# ADS1299_-_Breakout.net
KiCad netlist of a schematic drawn in EAGLE
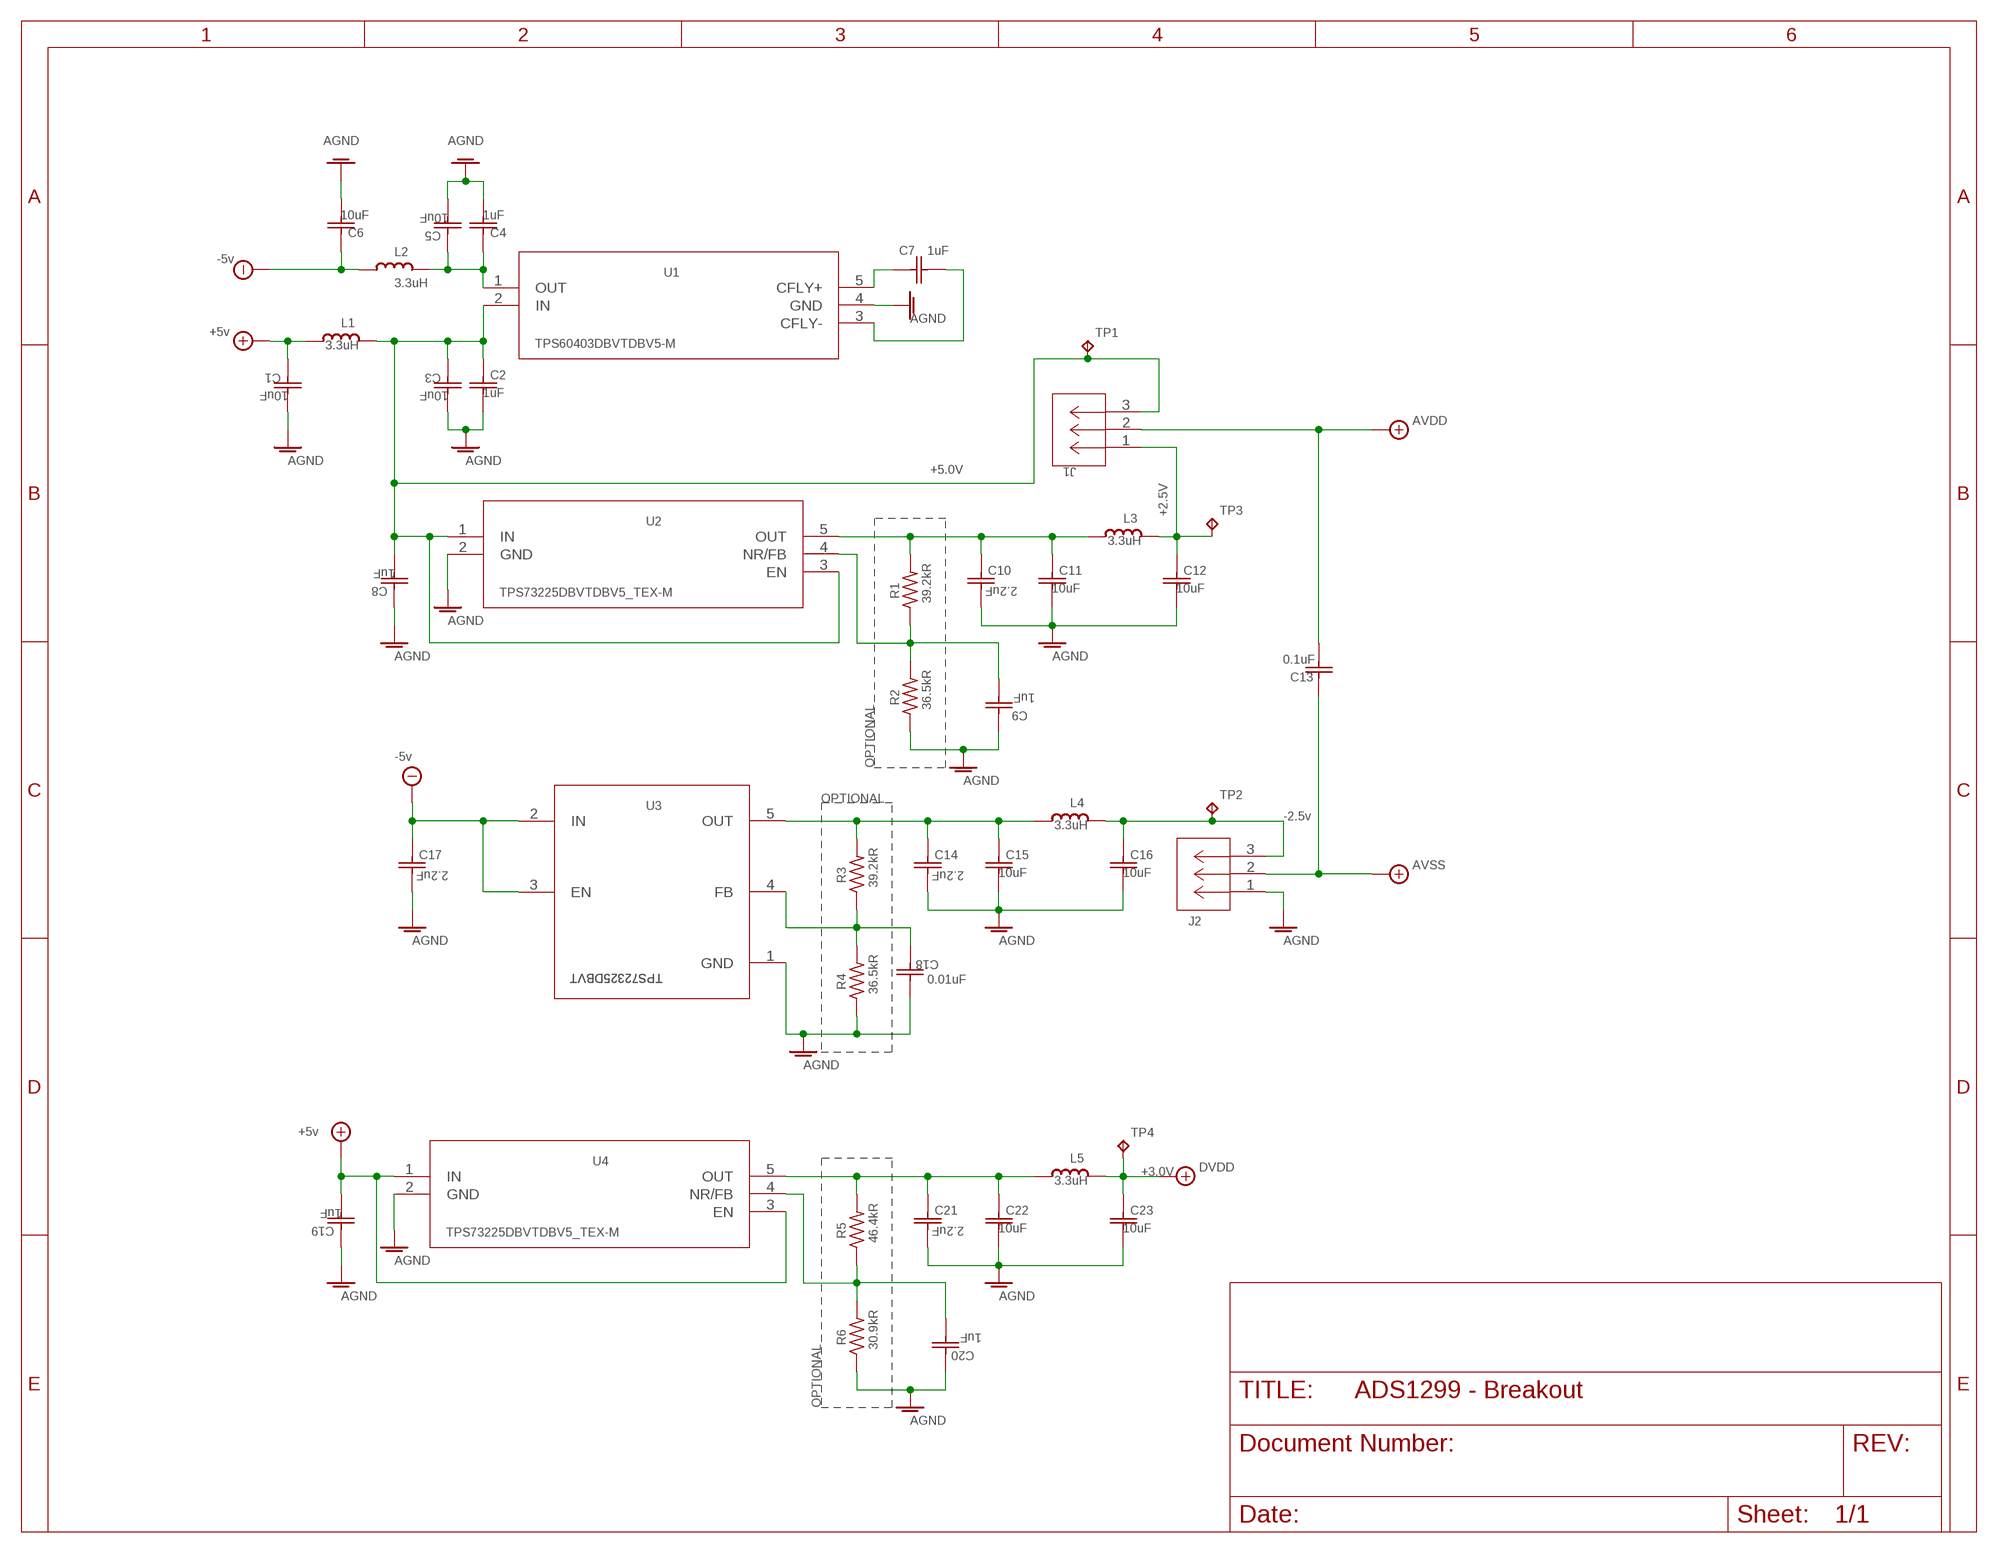
[diagram p0: schematic, sheet 1]

(export (version "E")
  (design (tool "Eeschema 10.0.6"))
  (components
    (comp (ref "C1")
      (value "10uF")
      (footprint "eagle-import:G-21_MUR-M")
      (fields
        (field (name "MANUFACTURER_PART_NUMBER") "GRM219R61A106KE44D")
        (field (name "COPYRIGHT") "Copyright (C) 2015 Accelerated Designs. All rights reserved")
      )
      (libsource (lib "eagle-import") (part "GRM219R61A106KE44DG-21_MUR-M"))
    )
    (comp (ref "C2")
      (value "1uF")
      (footprint "eagle-import:G-188_MUR-M")
      (fields
        (field (name "MANUFACTURER_PART_NUMBER") "GRM188R61E105KA12D")
        (field (name "COPYRIGHT") "Copyright (C) 2015 Accelerated Designs. All rights reserved")
      )
      (libsource (lib "eagle-import") (part "GRM188R61E105KA12DG-188_MUR-M"))
    )
    (comp (ref "C3")
      (value "10uF")
      (footprint "eagle-import:G-21_MUR-M")
      (fields
        (field (name "MANUFACTURER_PART_NUMBER") "GRM219R61A106KE44D")
        (field (name "COPYRIGHT") "Copyright (C) 2015 Accelerated Designs. All rights reserved")
      )
      (libsource (lib "eagle-import") (part "GRM219R61A106KE44DG-21_MUR-M"))
    )
    (comp (ref "C4")
      (value "1uF")
      (footprint "eagle-import:G-188_MUR-M")
      (fields
        (field (name "MANUFACTURER_PART_NUMBER") "GRM188R61E105KA12D")
        (field (name "COPYRIGHT") "Copyright (C) 2015 Accelerated Designs. All rights reserved")
      )
      (libsource (lib "eagle-import") (part "GRM188R61E105KA12DG-188_MUR-M"))
    )
    (comp (ref "C5")
      (value "10uF")
      (footprint "eagle-import:G-21_MUR-M")
      (fields
        (field (name "MANUFACTURER_PART_NUMBER") "GRM219R61A106KE44D")
        (field (name "COPYRIGHT") "Copyright (C) 2015 Accelerated Designs. All rights reserved")
      )
      (libsource (lib "eagle-import") (part "GRM219R61A106KE44DG-21_MUR-M"))
    )
    (comp (ref "C6")
      (value "10uF")
      (footprint "eagle-import:G-21_MUR-M")
      (fields
        (field (name "MANUFACTURER_PART_NUMBER") "GRM219R61A106KE44D")
        (field (name "COPYRIGHT") "Copyright (C) 2015 Accelerated Designs. All rights reserved")
      )
      (libsource (lib "eagle-import") (part "GRM219R61A106KE44DG-21_MUR-M"))
    )
    (comp (ref "C7")
      (value "1uF")
      (footprint "eagle-import:G-188_MUR-M")
      (fields
        (field (name "MANUFACTURER_PART_NUMBER") "GRM188R61E105KA12D")
        (field (name "COPYRIGHT") "Copyright (C) 2015 Accelerated Designs. All rights reserved")
      )
      (libsource (lib "eagle-import") (part "GRM188R61E105KA12DG-188_MUR-M"))
    )
    (comp (ref "C8")
      (value "1uF")
      (footprint "eagle-import:G-188_MUR-M")
      (fields
        (field (name "MANUFACTURER_PART_NUMBER") "GRM188R61E105KA12D")
        (field (name "COPYRIGHT") "Copyright (C) 2015 Accelerated Designs. All rights reserved")
      )
      (libsource (lib "eagle-import") (part "GRM188R61E105KA12DG-188_MUR-M"))
    )
    (comp (ref "C9")
      (value "1uF")
      (footprint "eagle-import:G-188_MUR-M")
      (fields
        (field (name "MANUFACTURER_PART_NUMBER") "GRM188R61E105KA12D")
        (field (name "COPYRIGHT") "Copyright (C) 2015 Accelerated Designs. All rights reserved")
      )
      (libsource (lib "eagle-import") (part "GRM188R61E105KA12DG-188_MUR-M"))
    )
    (comp (ref "C10")
      (value "2.2uF")
      (footprint "eagle-import:CAP_GCJ1888_MUR-M")
      (fields
        (field (name "MANUFACTURER_PART_NUMBER") "GRM185R60J225KE26D")
        (field (name "COPYRIGHT") "Copyright (C) 2015 Accelerated Designs. All rights reserved")
      )
      (libsource (lib "eagle-import") (part "GRM185R60J225KE26DCAP_GCJ1888_MUR-M"))
    )
    (comp (ref "C11")
      (value "10uF")
      (footprint "eagle-import:G-21_MUR-M")
      (fields
        (field (name "MANUFACTURER_PART_NUMBER") "GRM219R61A106KE44D")
        (field (name "COPYRIGHT") "Copyright (C) 2015 Accelerated Designs. All rights reserved")
      )
      (libsource (lib "eagle-import") (part "GRM219R61A106KE44DG-21_MUR-M"))
    )
    (comp (ref "C12")
      (value "10uF")
      (footprint "eagle-import:G-21_MUR-M")
      (fields
        (field (name "MANUFACTURER_PART_NUMBER") "GRM219R61A106KE44D")
        (field (name "COPYRIGHT") "Copyright (C) 2015 Accelerated Designs. All rights reserved")
      )
      (libsource (lib "eagle-import") (part "GRM219R61A106KE44DG-21_MUR-M"))
    )
    (comp (ref "C13")
      (value "0.1uF")
      (footprint "eagle-import:CAP_GRM_188_MUR-M")
      (fields
        (field (name "DIGIKEYPARTNUMBER") "490-1519-6-ND")
        (field (name "MANUFACTURER_PART_NUMBER") "GRM188R71H104KA93D")
        (field (name "TOLERANCE") "0.1")
        (field (name "COPYRIGHT") "Copyright (C) 2015 Accelerated Designs. All rights reserved")
      )
      (libsource (lib "eagle-import") (part "GRM188R71H104KA93DCAP_GRM_188_MUR-M"))
    )
    (comp (ref "C14")
      (value "2.2uF")
      (footprint "eagle-import:CAP_GCJ1888_MUR-M")
      (fields
        (field (name "MANUFACTURER_PART_NUMBER") "GRM185R60J225KE26D")
        (field (name "COPYRIGHT") "Copyright (C) 2015 Accelerated Designs. All rights reserved")
      )
      (libsource (lib "eagle-import") (part "GRM185R60J225KE26DCAP_GCJ1888_MUR-M"))
    )
    (comp (ref "C15")
      (value "10uF")
      (footprint "eagle-import:G-21_MUR-M")
      (fields
        (field (name "MANUFACTURER_PART_NUMBER") "GRM219R61A106KE44D")
        (field (name "COPYRIGHT") "Copyright (C) 2015 Accelerated Designs. All rights reserved")
      )
      (libsource (lib "eagle-import") (part "GRM219R61A106KE44DG-21_MUR-M"))
    )
    (comp (ref "C16")
      (value "10uF")
      (footprint "eagle-import:G-21_MUR-M")
      (fields
        (field (name "MANUFACTURER_PART_NUMBER") "GRM219R61A106KE44D")
        (field (name "COPYRIGHT") "Copyright (C) 2015 Accelerated Designs. All rights reserved")
      )
      (libsource (lib "eagle-import") (part "GRM219R61A106KE44DG-21_MUR-M"))
    )
    (comp (ref "C17")
      (value "2.2uF")
      (footprint "eagle-import:CAP_GCJ1888_MUR-M")
      (fields
        (field (name "MANUFACTURER_PART_NUMBER") "GRM185R60J225KE26D")
        (field (name "COPYRIGHT") "Copyright (C) 2015 Accelerated Designs. All rights reserved")
      )
      (libsource (lib "eagle-import") (part "GRM185R60J225KE26DCAP_GCJ1888_MUR-M"))
    )
    (comp (ref "C18")
      (value "0.01uF")
      (footprint "eagle-import:G-188_MUR-M")
      (fields
        (field (name "MANUFACTURER_PART_NUMBER") "GRM188R71H472KA01D")
        (field (name "COPYRIGHT") "Copyright (C) 2015 Accelerated Designs. All rights reserved")
      )
      (libsource (lib "eagle-import") (part "GRM188R71H472KA01DG-188_MUR-M"))
    )
    (comp (ref "C19")
      (value "1uF")
      (footprint "eagle-import:G-188_MUR-M")
      (fields
        (field (name "MANUFACTURER_PART_NUMBER") "GRM188R61E105KA12D")
        (field (name "COPYRIGHT") "Copyright (C) 2015 Accelerated Designs. All rights reserved")
      )
      (libsource (lib "eagle-import") (part "GRM188R61E105KA12DG-188_MUR-M"))
    )
    (comp (ref "C20")
      (value "1uF")
      (footprint "eagle-import:G-188_MUR-M")
      (fields
        (field (name "MANUFACTURER_PART_NUMBER") "GRM188R61E105KA12D")
        (field (name "COPYRIGHT") "Copyright (C) 2015 Accelerated Designs. All rights reserved")
      )
      (libsource (lib "eagle-import") (part "GRM188R61E105KA12DG-188_MUR-M"))
    )
    (comp (ref "C21")
      (value "2.2uF")
      (footprint "eagle-import:CAP_GCJ1888_MUR-M")
      (fields
        (field (name "MANUFACTURER_PART_NUMBER") "GRM185R60J225KE26D")
        (field (name "COPYRIGHT") "Copyright (C) 2015 Accelerated Designs. All rights reserved")
      )
      (libsource (lib "eagle-import") (part "GRM185R60J225KE26DCAP_GCJ1888_MUR-M"))
    )
    (comp (ref "C22")
      (value "10uF")
      (footprint "eagle-import:G-21_MUR-M")
      (fields
        (field (name "MANUFACTURER_PART_NUMBER") "GRM219R61A106KE44D")
        (field (name "COPYRIGHT") "Copyright (C) 2015 Accelerated Designs. All rights reserved")
      )
      (libsource (lib "eagle-import") (part "GRM219R61A106KE44DG-21_MUR-M"))
    )
    (comp (ref "C23")
      (value "10uF")
      (footprint "eagle-import:G-21_MUR-M")
      (fields
        (field (name "MANUFACTURER_PART_NUMBER") "GRM219R61A106KE44D")
        (field (name "COPYRIGHT") "Copyright (C) 2015 Accelerated Designs. All rights reserved")
      )
      (libsource (lib "eagle-import") (part "GRM219R61A106KE44DG-21_MUR-M"))
    )
    (comp (ref "J1")
      (value "TSW-103-07-T-S")
      (footprint "eagle-import:CON3_1X3_TU_TSW")
      (libsource (lib "eagle-import") (part "TSW-103-07-T-S"))
    )
    (comp (ref "J2")
      (value "TSW-103-07-T-S")
      (footprint "eagle-import:CON3_1X3_TU_TSW")
      (libsource (lib "eagle-import") (part "TSW-103-07-T-S"))
    )
    (comp (ref "L1")
      (value "3.3uH")
      (footprint "eagle-import:L0805")
      (libsource (lib "eagle-import") (part "L_0805"))
    )
    (comp (ref "L2")
      (value "3.3uH")
      (footprint "eagle-import:L0805")
      (libsource (lib "eagle-import") (part "L_0805"))
    )
    (comp (ref "L3")
      (value "3.3uH")
      (footprint "eagle-import:L0805")
      (libsource (lib "eagle-import") (part "L_0805"))
    )
    (comp (ref "L4")
      (value "3.3uH")
      (footprint "eagle-import:L0805")
      (libsource (lib "eagle-import") (part "L_0805"))
    )
    (comp (ref "L5")
      (value "3.3uH")
      (footprint "eagle-import:L0805")
      (libsource (lib "eagle-import") (part "L_0805"))
    )
    (comp (ref "R1")
      (value "39.2kR")
      (footprint "eagle-import:R0603")
      (libsource (lib "eagle-import") (part "R-US_R0603"))
    )
    (comp (ref "R2")
      (value "36.5kR")
      (footprint "eagle-import:R0603")
      (libsource (lib "eagle-import") (part "R-US_R0603"))
    )
    (comp (ref "R3")
      (value "39.2kR")
      (footprint "eagle-import:R0603")
      (libsource (lib "eagle-import") (part "R-US_R0603"))
    )
    (comp (ref "R4")
      (value "36.5kR")
      (footprint "eagle-import:R0603")
      (libsource (lib "eagle-import") (part "R-US_R0603"))
    )
    (comp (ref "R5")
      (value "46.4kR")
      (footprint "eagle-import:R0603")
      (libsource (lib "eagle-import") (part "R-US_R0603"))
    )
    (comp (ref "R6")
      (value "30.9kR")
      (footprint "eagle-import:R0603")
      (libsource (lib "eagle-import") (part "R-US_R0603"))
    )
    (comp (ref "TP1")
      (value "TP-040")
      (footprint "eagle-import:TP-040")
      (libsource (lib "eagle-import") (part "TP-040"))
    )
    (comp (ref "TP2")
      (value "TP-040")
      (footprint "eagle-import:TP-040")
      (libsource (lib "eagle-import") (part "TP-040"))
    )
    (comp (ref "TP3")
      (value "TP-040")
      (footprint "eagle-import:TP-040")
      (libsource (lib "eagle-import") (part "TP-040"))
    )
    (comp (ref "TP4")
      (value "TP-040")
      (footprint "eagle-import:TP-040")
      (libsource (lib "eagle-import") (part "TP-040"))
    )
    (comp (ref "U1")
      (value "TPS60403DBVTDBV5-M")
      (footprint "eagle-import:DBV5-M")
      (fields
        (field (name "GENERIC_PART_NUMBER") "TPS60403")
        (field (name "MANUFACTURER") "Texas Instruments")
        (field (name "MANUFACTURER_PART_NUMBER") "TPS60403DBVT")
      )
      (libsource (lib "eagle-import") (part "TPS60403DBVTDBV5-M"))
    )
    (comp (ref "U2")
      (value "TPS73225DBVTDBV5_TEX-M")
      (footprint "eagle-import:DBV5_TEX-M")
      (fields
        (field (name "MANUFACTURER") "Texas Instruments")
        (field (name "MANUFACTURER_PART_NUMBER") "TPS73225DBVT")
      )
      (libsource (lib "eagle-import") (part "TPS73225DBVTDBV5_TEX-M"))
    )
    (comp (ref "U3")
      (value "TPS72325DBVT")
      (footprint "eagle-import:DBV0005A")
      (fields (field (name "MANUFACTURER") "Texas Instruments") (field (name "PARTNUMBER") "TPS72301DBV"))
      (libsource (lib "eagle-import") (part "TPS72325DBVT"))
    )
    (comp (ref "U4")
      (value "TPS73225DBVTDBV5_TEX-M")
      (footprint "eagle-import:DBV5_TEX-M")
      (fields
        (field (name "MANUFACTURER") "Texas Instruments")
        (field (name "MANUFACTURER_PART_NUMBER") "TPS73225DBVT")
      )
      (libsource (lib "eagle-import") (part "TPS73225DBVTDBV5_TEX-M"))
    )
  )
  (nets
    (net (code "1") (name "+5v") (class "Default")
      (node (ref "C1") (pin "2") (pinfunction "2_2") (pintype "passive"))
      (node (ref "C13") (pin "1") (pinfunction "1_1") (pintype "passive"))
      (node (ref "C13") (pin "2") (pinfunction "2_2") (pintype "passive"))
      (node (ref "C19") (pin "1") (pinfunction "1_1") (pintype "passive"))
      (node (ref "J1") (pin "2") (pinfunction "2_2") (pintype "passive"))
      (node (ref "J2") (pin "2") (pinfunction "2_2") (pintype "passive"))
      (node (ref "L1") (pin "2") (pinfunction "2_2") (pintype "passive"))
      (node (ref "U4") (pin "1") (pinfunction "IN_1") (pintype "input"))
      (node (ref "U4") (pin "3") (pinfunction "EN_3") (pintype "passive"))
    )
    (net (code "2") (name "-5v") (class "Default")
      (node (ref "C17") (pin "2") (pinfunction "2_2") (pintype "passive"))
      (node (ref "C6") (pin "1") (pinfunction "1_1") (pintype "passive"))
      (node (ref "L2") (pin "2") (pinfunction "2_2") (pintype "passive"))
      (node (ref "U3") (pin "2") (pinfunction "IN_2") (pintype "power_in"))
      (node (ref "U3") (pin "3") (pinfunction "EN_3") (pintype "input"))
    )
    (net (code "3") (name "/+2.5V") (class "Default")
      (node (ref "C12") (pin "2") (pinfunction "2_2") (pintype "passive"))
      (node (ref "J1") (pin "1") (pinfunction "1_1") (pintype "passive"))
      (node (ref "L3") (pin "1") (pinfunction "1_1") (pintype "passive"))
      (node (ref "TP3") (pin "1") (pinfunction "1_1") (pintype "passive"))
    )
    (net (code "4") (name "AGND") (class "Default")
      (node (ref "C1") (pin "1") (pinfunction "1_1") (pintype "passive"))
      (node (ref "C10") (pin "1") (pinfunction "1_1") (pintype "passive"))
      (node (ref "C11") (pin "1") (pinfunction "1_1") (pintype "passive"))
      (node (ref "C12") (pin "1") (pinfunction "1_1") (pintype "passive"))
      (node (ref "C14") (pin "1") (pinfunction "1_1") (pintype "passive"))
      (node (ref "C15") (pin "1") (pinfunction "1_1") (pintype "passive"))
      (node (ref "C16") (pin "1") (pinfunction "1_1") (pintype "passive"))
      (node (ref "C17") (pin "1") (pinfunction "1_1") (pintype "passive"))
      (node (ref "C18") (pin "1") (pinfunction "1_1") (pintype "passive"))
      (node (ref "C19") (pin "2") (pinfunction "2_2") (pintype "passive"))
      (node (ref "C2") (pin "2") (pinfunction "2_2") (pintype "passive"))
      (node (ref "C20") (pin "2") (pinfunction "2_2") (pintype "passive"))
      (node (ref "C21") (pin "1") (pinfunction "1_1") (pintype "passive"))
      (node (ref "C22") (pin "1") (pinfunction "1_1") (pintype "passive"))
      (node (ref "C23") (pin "1") (pinfunction "1_1") (pintype "passive"))
      (node (ref "C3") (pin "2") (pinfunction "2_2") (pintype "passive"))
      (node (ref "C4") (pin "2") (pinfunction "2_2") (pintype "passive"))
      (node (ref "C5") (pin "2") (pinfunction "2_2") (pintype "passive"))
      (node (ref "C6") (pin "2") (pinfunction "2_2") (pintype "passive"))
      (node (ref "C8") (pin "2") (pinfunction "2_2") (pintype "passive"))
      (node (ref "C9") (pin "2") (pinfunction "2_2") (pintype "passive"))
      (node (ref "J2") (pin "1") (pinfunction "1_1") (pintype "passive"))
      (node (ref "R2") (pin "1") (pinfunction "1_1") (pintype "passive"))
      (node (ref "R4") (pin "1") (pinfunction "1_1") (pintype "passive"))
      (node (ref "R6") (pin "1") (pinfunction "1_1") (pintype "passive"))
      (node (ref "U1") (pin "4") (pinfunction "GND_4") (pintype "power_in"))
      (node (ref "U2") (pin "2") (pinfunction "GND_2") (pintype "power_in"))
      (node (ref "U3") (pin "1") (pinfunction "GND_1") (pintype "power_in"))
      (node (ref "U4") (pin "2") (pinfunction "GND_2") (pintype "power_in"))
    )
    (net (code "5") (name "DVDD") (class "Default")
      (node (ref "C23") (pin "2") (pinfunction "2_2") (pintype "passive"))
      (node (ref "L5") (pin "1") (pinfunction "1_1") (pintype "passive"))
      (node (ref "TP4") (pin "1") (pinfunction "1_1") (pintype "passive"))
    )
    (net (code "6") (name "Net-(C16-Pad2)") (class "Default")
      (node (ref "C16") (pin "2") (pinfunction "2_2") (pintype "passive"))
      (node (ref "J2") (pin "3") (pinfunction "3_3") (pintype "passive"))
      (node (ref "L4") (pin "1") (pinfunction "1_1") (pintype "passive"))
      (node (ref "TP2") (pin "1") (pinfunction "1_1") (pintype "passive"))
    )
    (net (code "7") (name "Net-(U1-CFLY+)") (class "Default")
      (node (ref "C7") (pin "2") (pinfunction "2_2") (pintype "passive"))
      (node (ref "U1") (pin "5") (pinfunction "CFLY+_5") (pintype "passive"))
    )
    (net (code "8") (name "Net-(U1-CFLY-)") (class "Default")
      (node (ref "C7") (pin "1") (pinfunction "1_1") (pintype "passive"))
      (node (ref "U1") (pin "3") (pinfunction "CFLY-_3") (pintype "passive"))
    )
    (net (code "9") (name "Net-(U1-IN)") (class "Default")
      (node (ref "C2") (pin "1") (pinfunction "1_1") (pintype "passive"))
      (node (ref "C3") (pin "1") (pinfunction "1_1") (pintype "passive"))
      (node (ref "C8") (pin "1") (pinfunction "1_1") (pintype "passive"))
      (node (ref "J1") (pin "3") (pinfunction "3_3") (pintype "passive"))
      (node (ref "L1") (pin "1") (pinfunction "1_1") (pintype "passive"))
      (node (ref "TP1") (pin "1") (pinfunction "1_1") (pintype "passive"))
      (node (ref "U1") (pin "2") (pinfunction "IN_2") (pintype "input"))
      (node (ref "U2") (pin "1") (pinfunction "IN_1") (pintype "input"))
      (node (ref "U2") (pin "3") (pinfunction "EN_3") (pintype "passive"))
    )
    (net (code "10") (name "Net-(U1-OUT)") (class "Default")
      (node (ref "C4") (pin "1") (pinfunction "1_1") (pintype "passive"))
      (node (ref "C5") (pin "1") (pinfunction "1_1") (pintype "passive"))
      (node (ref "L2") (pin "1") (pinfunction "1_1") (pintype "passive"))
      (node (ref "U1") (pin "1") (pinfunction "OUT_1") (pintype "output"))
    )
    (net (code "11") (name "Net-(U2-NR{slash}FB)") (class "Default")
      (node (ref "C9") (pin "1") (pinfunction "1_1") (pintype "passive"))
      (node (ref "R1") (pin "1") (pinfunction "1_1") (pintype "passive"))
      (node (ref "R2") (pin "2") (pinfunction "2_2") (pintype "passive"))
      (node (ref "U2") (pin "4") (pinfunction "NR/FB_4") (pintype "bidirectional"))
    )
    (net (code "12") (name "Net-(U2-OUT)") (class "Default")
      (node (ref "C10") (pin "2") (pinfunction "2_2") (pintype "passive"))
      (node (ref "C11") (pin "2") (pinfunction "2_2") (pintype "passive"))
      (node (ref "L3") (pin "2") (pinfunction "2_2") (pintype "passive"))
      (node (ref "R1") (pin "2") (pinfunction "2_2") (pintype "passive"))
      (node (ref "U2") (pin "5") (pinfunction "OUT_5") (pintype "output"))
    )
    (net (code "13") (name "Net-(U3-FB)") (class "Default")
      (node (ref "C18") (pin "2") (pinfunction "2_2") (pintype "passive"))
      (node (ref "R3") (pin "1") (pinfunction "1_1") (pintype "passive"))
      (node (ref "R4") (pin "2") (pinfunction "2_2") (pintype "passive"))
      (node (ref "U3") (pin "4") (pinfunction "FB_4") (pintype "input"))
    )
    (net (code "14") (name "Net-(U3-OUT)") (class "Default")
      (node (ref "C14") (pin "2") (pinfunction "2_2") (pintype "passive"))
      (node (ref "C15") (pin "2") (pinfunction "2_2") (pintype "passive"))
      (node (ref "L4") (pin "2") (pinfunction "2_2") (pintype "passive"))
      (node (ref "R3") (pin "2") (pinfunction "2_2") (pintype "passive"))
      (node (ref "U3") (pin "5") (pinfunction "OUT_5") (pintype "power_in"))
    )
    (net (code "15") (name "Net-(U4-NR{slash}FB)") (class "Default")
      (node (ref "C20") (pin "1") (pinfunction "1_1") (pintype "passive"))
      (node (ref "R5") (pin "1") (pinfunction "1_1") (pintype "passive"))
      (node (ref "R6") (pin "2") (pinfunction "2_2") (pintype "passive"))
      (node (ref "U4") (pin "4") (pinfunction "NR/FB_4") (pintype "bidirectional"))
    )
    (net (code "16") (name "Net-(U4-OUT)") (class "Default")
      (node (ref "C21") (pin "2") (pinfunction "2_2") (pintype "passive"))
      (node (ref "C22") (pin "2") (pinfunction "2_2") (pintype "passive"))
      (node (ref "L5") (pin "2") (pinfunction "2_2") (pintype "passive"))
      (node (ref "R5") (pin "2") (pinfunction "2_2") (pintype "passive"))
      (node (ref "U4") (pin "5") (pinfunction "OUT_5") (pintype "output"))
    )
  )
)
